# team_flagNEW.net
KiCad netlist of a schematic drawn in EAGLE
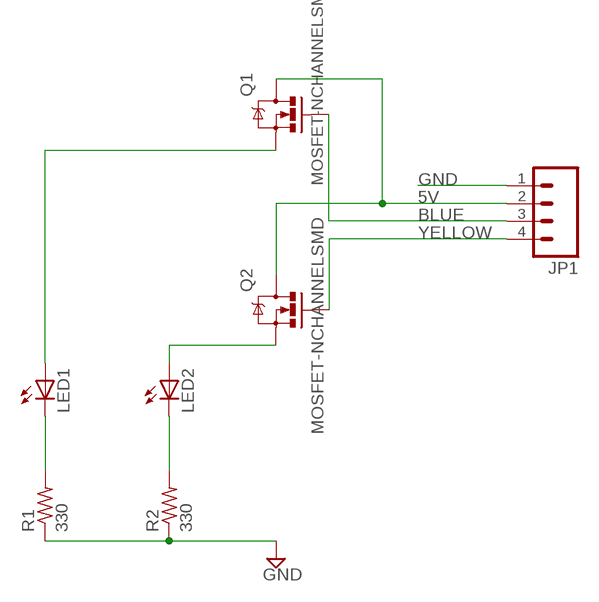
[diagram p0: schematic, sheet 1]

(export (version "E")
  (design (tool "Eeschema 10.0.6"))
  (components
    (comp (ref "JP1")
      (value "M04PTH")
      (footprint "eagle-import:1X04")
      (libsource (lib "eagle-import") (part "M04PTH"))
    )
    (comp (ref "LED1")
      (value "LED5MM")
      (footprint "eagle-import:LED5MM")
      (libsource (lib "eagle-import") (part "LED5MM"))
    )
    (comp (ref "LED2")
      (value "LED5MM")
      (footprint "eagle-import:LED5MM")
      (libsource (lib "eagle-import") (part "LED5MM"))
    )
    (comp (ref "Q1")
      (value "MOSFET-NCHANNELSMD")
      (footprint "eagle-import:SOT23-3")
      (libsource (lib "eagle-import") (part "MOSFET-NCHANNELSMD"))
    )
    (comp (ref "Q2")
      (value "MOSFET-NCHANNELSMD")
      (footprint "eagle-import:SOT23-3")
      (libsource (lib "eagle-import") (part "MOSFET-NCHANNELSMD"))
    )
    (comp (ref "R1")
      (value "330")
      (footprint "eagle-import:R0603")
      (libsource (lib "eagle-import") (part "R-US_R0603"))
    )
    (comp (ref "R2")
      (value "330")
      (footprint "eagle-import:R0603")
      (libsource (lib "eagle-import") (part "R-US_R0603"))
    )
  )
  (nets
    (net (code "1") (name "/5V") (class "Default")
      (node (ref "JP1") (pin "2") (pinfunction "2_2") (pintype "passive"))
      (node (ref "Q1") (pin "3") (pinfunction "D_3") (pintype "passive"))
      (node (ref "Q2") (pin "3") (pinfunction "D_3") (pintype "passive"))
    )
    (net (code "2") (name "/BLUE") (class "Default")
      (node (ref "JP1") (pin "3") (pinfunction "3_3") (pintype "passive"))
      (node (ref "Q1") (pin "1") (pinfunction "G_1") (pintype "passive"))
    )
    (net (code "3") (name "/YELLOW") (class "Default")
      (node (ref "JP1") (pin "4") (pinfunction "4_4") (pintype "passive"))
      (node (ref "Q2") (pin "1") (pinfunction "G_1") (pintype "passive"))
    )
    (net (code "4") (name "GND") (class "Default")
      (node (ref "JP1") (pin "1") (pinfunction "1_1") (pintype "passive"))
      (node (ref "R1") (pin "1") (pinfunction "1_1") (pintype "passive"))
      (node (ref "R2") (pin "1") (pinfunction "1_1") (pintype "passive"))
    )
    (net (code "5") (name "Net-(LED1-C)") (class "Default")
      (node (ref "LED1") (pin "K") (pinfunction "C_K") (pintype "passive"))
      (node (ref "R1") (pin "2") (pinfunction "2_2") (pintype "passive"))
    )
    (net (code "6") (name "Net-(LED2-C)") (class "Default")
      (node (ref "LED2") (pin "K") (pinfunction "C_K") (pintype "passive"))
      (node (ref "R2") (pin "2") (pinfunction "2_2") (pintype "passive"))
    )
    (net (code "7") (name "Net-(Q1-S)") (class "Default")
      (node (ref "LED1") (pin "A") (pinfunction "A_A") (pintype "passive"))
      (node (ref "Q1") (pin "2") (pinfunction "S_2") (pintype "passive"))
    )
    (net (code "8") (name "Net-(Q2-S)") (class "Default")
      (node (ref "LED2") (pin "A") (pinfunction "A_A") (pintype "passive"))
      (node (ref "Q2") (pin "2") (pinfunction "S_2") (pintype "passive"))
    )
  )
)
